# Kaleidoscope.net
KiCad netlist of a schematic drawn in EasyEDA Pro
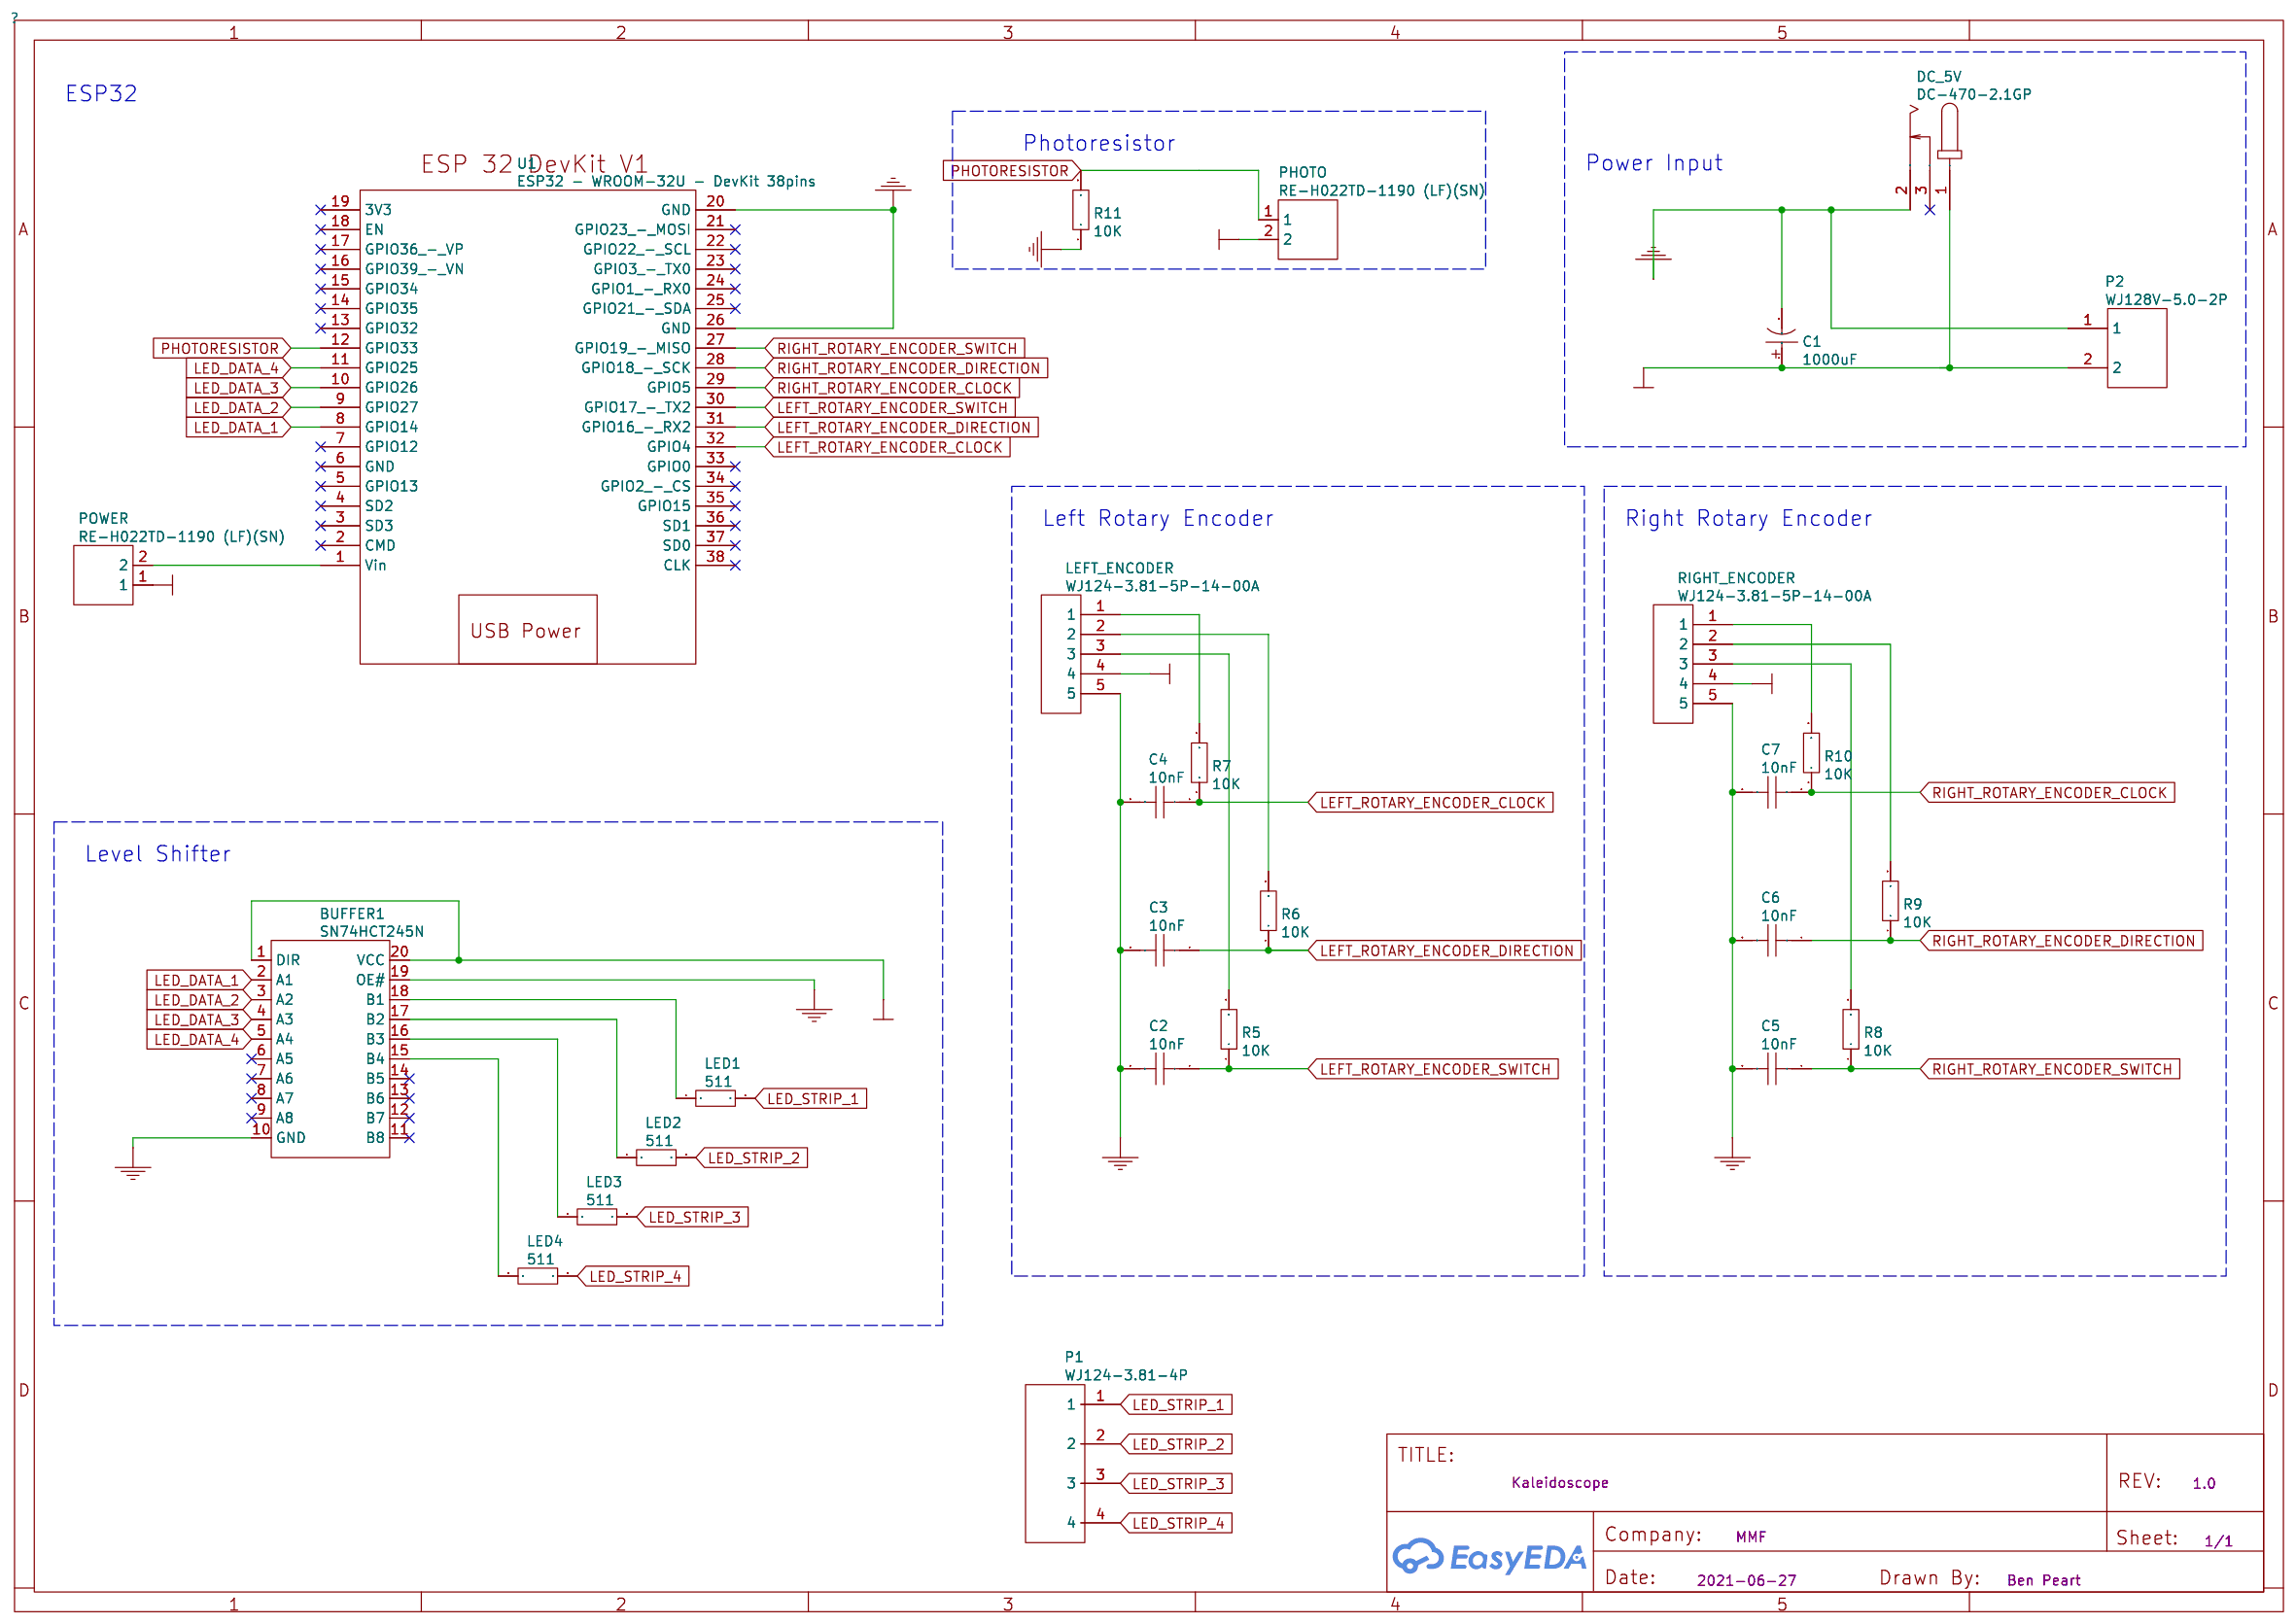
[diagram p0: schematic sheet]

(export (version "E")
  (design (tool "Eeschema 10.0.6"))
  (components
    (comp (ref "BUFFER1")
      (value "SN74HCT245N")
      (footprint "easyedapro:DIP-20_L26.8-W6.4-P2.54-LS7.6-BL")
      (fields (field (name "Manufacturer") "Texas Instruments"))
      (libsource (lib "easyedapro") (part "SN74HCT245N"))
    )
    (comp (ref "C1")
      (value "1000uF")
      (footprint "easyedapro:CAP-TH_BD10.0-P5.00-D1.0-FD")
      (fields (field (name "Manufacturer Part") "25YXJ1000M10X20") (field (name "Manufacturer") "Rubycon"))
      (libsource (lib "easyedapro") (part "1000uF"))
    )
    (comp (ref "C2")
      (value "10nF")
      (footprint "easyedapro:CAP-TH_L5.0-W2.5-P2.54-D0.7")
      (fields
        (field (name "Manufacturer Part") "CC1H103ZA1AD3F4D10MF")
        (field (name "Manufacturer") "Dersonic")
      )
      (libsource (lib "easyedapro") (part "10nF"))
    )
    (comp (ref "C3")
      (value "10nF")
      (footprint "easyedapro:CAP-TH_L5.0-W2.5-P2.54-D0.7")
      (fields
        (field (name "Manufacturer Part") "CC1H103ZA1AD3F4D10MF")
        (field (name "Manufacturer") "Dersonic")
      )
      (libsource (lib "easyedapro") (part "10nF"))
    )
    (comp (ref "C4")
      (value "10nF")
      (footprint "easyedapro:CAP-TH_L5.0-W2.5-P2.54-D0.7")
      (fields
        (field (name "Manufacturer Part") "CC1H103ZA1AD3F4D10MF")
        (field (name "Manufacturer") "Dersonic")
      )
      (libsource (lib "easyedapro") (part "10nF"))
    )
    (comp (ref "C5")
      (value "10nF")
      (footprint "easyedapro:CAP-TH_L5.0-W2.5-P2.54-D0.7")
      (fields
        (field (name "Manufacturer Part") "CC1H103ZA1AD3F4D10MF")
        (field (name "Manufacturer") "Dersonic")
      )
      (libsource (lib "easyedapro") (part "10nF"))
    )
    (comp (ref "C6")
      (value "10nF")
      (footprint "easyedapro:CAP-TH_L5.0-W2.5-P2.54-D0.7")
      (fields
        (field (name "Manufacturer Part") "CC1H103ZA1AD3F4D10MF")
        (field (name "Manufacturer") "Dersonic")
      )
      (libsource (lib "easyedapro") (part "10nF"))
    )
    (comp (ref "C7")
      (value "10nF")
      (footprint "easyedapro:CAP-TH_L5.0-W2.5-P2.54-D0.7")
      (fields
        (field (name "Manufacturer Part") "CC1H103ZA1AD3F4D10MF")
        (field (name "Manufacturer") "Dersonic")
      )
      (libsource (lib "easyedapro") (part "10nF"))
    )
    (comp (ref "DC_5V")
      (value "DC-470-2.1GP")
      (footprint "easyedapro:DC-IN-TH_DC-470-2.1GP")
      (fields (field (name "Manufacturer") "GANGYUAN"))
      (libsource (lib "easyedapro") (part "DC-470-2.1GP"))
    )
    (comp (ref "LED1")
      (value "511")
      (footprint "easyedapro:R0603")
      (fields (field (name "Manufacturer Part") "RC0603FR-07511RL") (field (name "Manufacturer") "YAGEO"))
      (libsource (lib "easyedapro") (part "511"))
    )
    (comp (ref "LED2")
      (value "511")
      (footprint "easyedapro:R0603")
      (fields (field (name "Manufacturer Part") "RC0603FR-07511RL") (field (name "Manufacturer") "YAGEO"))
      (libsource (lib "easyedapro") (part "511"))
    )
    (comp (ref "LED3")
      (value "511")
      (footprint "easyedapro:R0603")
      (fields (field (name "Manufacturer Part") "RC0603FR-07511RL") (field (name "Manufacturer") "YAGEO"))
      (libsource (lib "easyedapro") (part "511"))
    )
    (comp (ref "LED4")
      (value "511")
      (footprint "easyedapro:R0603")
      (fields (field (name "Manufacturer Part") "RC0603FR-07511RL") (field (name "Manufacturer") "YAGEO"))
      (libsource (lib "easyedapro") (part "511"))
    )
    (comp (ref "LEFT_ENCODER")
      (value "WJ124-3.81-5P-14-00A")
      (footprint "easyedapro:CONN-TH_5P-P3.81_KF124-3.81-5P")
      (fields (field (name "Manufacturer") "ReliaPro"))
      (libsource (lib "easyedapro") (part "WJ124-3.81-5P-14-00A"))
    )
    (comp (ref "P1")
      (value "WJ124-3.81-4P")
      (footprint "easyedapro:CONN-TH_4P-P3.81_KF124-3.81-4P")
      (fields (field (name "Manufacturer") "ReliaPro"))
      (libsource (lib "easyedapro") (part "WJ124-3.81-4P"))
    )
    (comp (ref "P2")
      (value "WJ128V-5.0-2P")
      (footprint "easyedapro:CONN-TH_2P-P5.00_WJ128V-5.0-2P")
      (fields (field (name "Manufacturer") "ReliaPro"))
      (libsource (lib "easyedapro") (part "WJ128V-5.0-2P"))
    )
    (comp (ref "PHOTO")
      (value "RE-H022TD-1190 (LF)(SN)")
      (footprint "easyedapro:HDR-TH_2P-P2.54-V")
      (fields (field (name "Manufacturer") "JST Sales America"))
      (libsource (lib "easyedapro") (part "RE-H022TD-1190 (LF)(SN)"))
    )
    (comp (ref "POWER")
      (value "RE-H022TD-1190 (LF)(SN)")
      (footprint "easyedapro:HDR-TH_2P-P2.54-V")
      (fields (field (name "Manufacturer") "JST Sales America"))
      (libsource (lib "easyedapro") (part "RE-H022TD-1190 (LF)(SN)"))
    )
    (comp (ref "R5")
      (value "10K")
      (footprint "easyedapro:R0603")
      (fields (field (name "Manufacturer Part") "ARG03FTC1002") (field (name "Manufacturer") "Viking Tech"))
      (libsource (lib "easyedapro") (part "10K"))
    )
    (comp (ref "R6")
      (value "10K")
      (footprint "easyedapro:R0603")
      (fields (field (name "Manufacturer Part") "ARG03FTC1002") (field (name "Manufacturer") "Viking Tech"))
      (libsource (lib "easyedapro") (part "10K"))
    )
    (comp (ref "R7")
      (value "10K")
      (footprint "easyedapro:R0603")
      (fields (field (name "Manufacturer Part") "ARG03FTC1002") (field (name "Manufacturer") "Viking Tech"))
      (libsource (lib "easyedapro") (part "10K"))
    )
    (comp (ref "R8")
      (value "10K")
      (footprint "easyedapro:R0603")
      (fields (field (name "Manufacturer Part") "ARG03FTC1002") (field (name "Manufacturer") "Viking Tech"))
      (libsource (lib "easyedapro") (part "10K"))
    )
    (comp (ref "R9")
      (value "10K")
      (footprint "easyedapro:R0603")
      (fields (field (name "Manufacturer Part") "ARG03FTC1002") (field (name "Manufacturer") "Viking Tech"))
      (libsource (lib "easyedapro") (part "10K"))
    )
    (comp (ref "R10")
      (value "10K")
      (footprint "easyedapro:R0603")
      (fields (field (name "Manufacturer Part") "ARG03FTC1002") (field (name "Manufacturer") "Viking Tech"))
      (libsource (lib "easyedapro") (part "10K"))
    )
    (comp (ref "R11")
      (value "10K")
      (footprint "easyedapro:R0603")
      (fields (field (name "Manufacturer Part") "ARG03FTC1002") (field (name "Manufacturer") "Viking Tech"))
      (libsource (lib "easyedapro") (part "10K"))
    )
    (comp (ref "RIGHT_ENCODER")
      (value "WJ124-3.81-5P-14-00A")
      (footprint "easyedapro:CONN-TH_5P-P3.81_KF124-3.81-5P")
      (fields (field (name "Manufacturer") "ReliaPro"))
      (libsource (lib "easyedapro") (part "WJ124-3.81-5P-14-00A"))
    )
    (comp (ref "U1")
      (value "ESP32 - WROOM-32U - DevKit 38pins")
      (footprint "easyedapro:ESP32 - WROOM-32U - DEVVKIT 38PIN")
      (libsource (lib "easyedapro") (part "ESP32 - WROOM-32U - DevKit 38pins"))
    )
  )
  (nets
    (net (code "1") (name "+5V") (class "Default")
      (node (ref "BUFFER1") (pin "1") (pinfunction "DIR_1") (pintype "unspecified"))
      (node (ref "BUFFER1") (pin "20") (pinfunction "VCC_20") (pintype "unspecified"))
      (node (ref "C1") (pin "1") (pinfunction "1_1") (pintype "input"))
      (node (ref "DC_5V") (pin "1") (pinfunction "1_1") (pintype "unspecified"))
      (node (ref "LEFT_ENCODER") (pin "4") (pinfunction "4_4") (pintype "unspecified"))
      (node (ref "P2") (pin "2") (pinfunction "2_2") (pintype "unspecified"))
      (node (ref "PHOTO") (pin "2") (pinfunction "2_2") (pintype "unspecified"))
      (node (ref "POWER") (pin "1") (pinfunction "1_1") (pintype "unspecified"))
      (node (ref "RIGHT_ENCODER") (pin "4") (pinfunction "4_4") (pintype "unspecified"))
    )
    (net (code "2") (name "GND") (class "Default")
      (node (ref "BUFFER1") (pin "10") (pinfunction "GND_10") (pintype "unspecified"))
      (node (ref "BUFFER1") (pin "19") (pinfunction "OE#_19") (pintype "unspecified"))
      (node (ref "C1") (pin "2") (pinfunction "2_2") (pintype "input"))
      (node (ref "C2") (pin "2") (pinfunction "2_2") (pintype "unspecified"))
      (node (ref "C3") (pin "2") (pinfunction "2_2") (pintype "unspecified"))
      (node (ref "C4") (pin "2") (pinfunction "2_2") (pintype "unspecified"))
      (node (ref "C5") (pin "2") (pinfunction "2_2") (pintype "unspecified"))
      (node (ref "C6") (pin "2") (pinfunction "2_2") (pintype "unspecified"))
      (node (ref "C7") (pin "2") (pinfunction "2_2") (pintype "unspecified"))
      (node (ref "DC_5V") (pin "2") (pinfunction "2_2") (pintype "unspecified"))
      (node (ref "LEFT_ENCODER") (pin "5") (pinfunction "5_5") (pintype "unspecified"))
      (node (ref "P2") (pin "1") (pinfunction "1_1") (pintype "unspecified"))
      (node (ref "R11") (pin "1") (pinfunction "1_1") (pintype "unspecified"))
      (node (ref "RIGHT_ENCODER") (pin "5") (pinfunction "5_5") (pintype "unspecified"))
      (node (ref "U1") (pin "20") (pinfunction "GND_20") (pintype "unspecified"))
      (node (ref "U1") (pin "26") (pinfunction "GND_26") (pintype "unspecified"))
    )
    (net (code "3") (name "LED_DATA_1") (class "Default")
      (node (ref "BUFFER1") (pin "2") (pinfunction "A1_2") (pintype "unspecified"))
      (node (ref "U1") (pin "8") (pinfunction "GPIO14_8") (pintype "unspecified"))
    )
    (net (code "4") (name "LED_DATA_2") (class "Default")
      (node (ref "BUFFER1") (pin "3") (pinfunction "A2_3") (pintype "unspecified"))
      (node (ref "U1") (pin "9") (pinfunction "GPIO27_9") (pintype "unspecified"))
    )
    (net (code "5") (name "LED_DATA_3") (class "Default")
      (node (ref "BUFFER1") (pin "4") (pinfunction "A3_4") (pintype "unspecified"))
      (node (ref "U1") (pin "10") (pinfunction "GPIO26_10") (pintype "unspecified"))
    )
    (net (code "6") (name "LED_DATA_4") (class "Default")
      (node (ref "BUFFER1") (pin "5") (pinfunction "A4_5") (pintype "unspecified"))
      (node (ref "U1") (pin "11") (pinfunction "GPIO25_11") (pintype "unspecified"))
    )
    (net (code "7") (name "LED_STRIP_1") (class "Default")
      (node (ref "LED1") (pin "2") (pinfunction "2_2") (pintype "input"))
      (node (ref "P1") (pin "1") (pinfunction "1_1") (pintype "input"))
    )
    (net (code "8") (name "LED_STRIP_2") (class "Default")
      (node (ref "LED2") (pin "2") (pinfunction "2_2") (pintype "input"))
      (node (ref "P1") (pin "2") (pinfunction "2_2") (pintype "input"))
    )
    (net (code "9") (name "LED_STRIP_3") (class "Default")
      (node (ref "LED3") (pin "2") (pinfunction "2_2") (pintype "input"))
      (node (ref "P1") (pin "3") (pinfunction "3_3") (pintype "input"))
    )
    (net (code "10") (name "LED_STRIP_4") (class "Default")
      (node (ref "LED4") (pin "2") (pinfunction "2_2") (pintype "input"))
      (node (ref "P1") (pin "4") (pinfunction "4_4") (pintype "input"))
    )
    (net (code "11") (name "LEFT_ROTARY_ENCODER_CLOCK") (class "Default")
      (node (ref "C4") (pin "1") (pinfunction "1_1") (pintype "unspecified"))
      (node (ref "R7") (pin "1") (pinfunction "1_1") (pintype "unspecified"))
      (node (ref "U1") (pin "32") (pinfunction "GPIO4_32") (pintype "unspecified"))
    )
    (net (code "12") (name "LEFT_ROTARY_ENCODER_DIRECTION") (class "Default")
      (node (ref "C3") (pin "1") (pinfunction "1_1") (pintype "unspecified"))
      (node (ref "R6") (pin "1") (pinfunction "1_1") (pintype "unspecified"))
      (node (ref "U1") (pin "31") (pinfunction "GPIO16_-_RX2_31") (pintype "unspecified"))
    )
    (net (code "13") (name "LEFT_ROTARY_ENCODER_SWITCH") (class "Default")
      (node (ref "C2") (pin "1") (pinfunction "1_1") (pintype "unspecified"))
      (node (ref "R5") (pin "1") (pinfunction "1_1") (pintype "unspecified"))
      (node (ref "U1") (pin "30") (pinfunction "GPIO17_-_TX2_30") (pintype "unspecified"))
    )
    (net (code "14") (name "Net-(BUFFER1-B1)") (class "Default")
      (node (ref "BUFFER1") (pin "18") (pinfunction "B1_18") (pintype "unspecified"))
      (node (ref "LED1") (pin "1") (pinfunction "1_1") (pintype "input"))
    )
    (net (code "15") (name "Net-(BUFFER1-B2)") (class "Default")
      (node (ref "BUFFER1") (pin "17") (pinfunction "B2_17") (pintype "unspecified"))
      (node (ref "LED2") (pin "1") (pinfunction "1_1") (pintype "input"))
    )
    (net (code "16") (name "Net-(BUFFER1-B3)") (class "Default")
      (node (ref "BUFFER1") (pin "16") (pinfunction "B3_16") (pintype "unspecified"))
      (node (ref "LED3") (pin "1") (pinfunction "1_1") (pintype "input"))
    )
    (net (code "17") (name "Net-(BUFFER1-B4)") (class "Default")
      (node (ref "BUFFER1") (pin "15") (pinfunction "B4_15") (pintype "unspecified"))
      (node (ref "LED4") (pin "1") (pinfunction "1_1") (pintype "input"))
    )
    (net (code "18") (name "Net-(LEFT_ENCODER-Pad1)") (class "Default")
      (node (ref "LEFT_ENCODER") (pin "1") (pinfunction "1_1") (pintype "unspecified"))
      (node (ref "R7") (pin "2") (pinfunction "2_2") (pintype "unspecified"))
    )
    (net (code "19") (name "Net-(LEFT_ENCODER-Pad2)") (class "Default")
      (node (ref "LEFT_ENCODER") (pin "2") (pinfunction "2_2") (pintype "unspecified"))
      (node (ref "R6") (pin "2") (pinfunction "2_2") (pintype "unspecified"))
    )
    (net (code "20") (name "Net-(LEFT_ENCODER-Pad3)") (class "Default")
      (node (ref "LEFT_ENCODER") (pin "3") (pinfunction "3_3") (pintype "unspecified"))
      (node (ref "R5") (pin "2") (pinfunction "2_2") (pintype "unspecified"))
    )
    (net (code "21") (name "Net-(R8-Pad2)") (class "Default")
      (node (ref "R8") (pin "2") (pinfunction "2_2") (pintype "unspecified"))
      (node (ref "RIGHT_ENCODER") (pin "3") (pinfunction "3_3") (pintype "unspecified"))
    )
    (net (code "22") (name "Net-(R9-Pad2)") (class "Default")
      (node (ref "R9") (pin "2") (pinfunction "2_2") (pintype "unspecified"))
      (node (ref "RIGHT_ENCODER") (pin "2") (pinfunction "2_2") (pintype "unspecified"))
    )
    (net (code "23") (name "Net-(R10-Pad2)") (class "Default")
      (node (ref "R10") (pin "2") (pinfunction "2_2") (pintype "unspecified"))
      (node (ref "RIGHT_ENCODER") (pin "1") (pinfunction "1_1") (pintype "unspecified"))
    )
    (net (code "24") (name "Net-(U1-Vin)") (class "Default")
      (node (ref "POWER") (pin "2") (pinfunction "2_2") (pintype "unspecified"))
      (node (ref "U1") (pin "1") (pinfunction "Vin_1") (pintype "unspecified"))
    )
    (net (code "25") (name "PHOTORESISTOR") (class "Default")
      (node (ref "PHOTO") (pin "1") (pinfunction "1_1") (pintype "unspecified"))
      (node (ref "R11") (pin "2") (pinfunction "2_2") (pintype "unspecified"))
      (node (ref "U1") (pin "12") (pinfunction "GPIO33_12") (pintype "unspecified"))
    )
    (net (code "26") (name "RIGHT_ROTARY_ENCODER_CLOCK") (class "Default")
      (node (ref "C7") (pin "1") (pinfunction "1_1") (pintype "unspecified"))
      (node (ref "R10") (pin "1") (pinfunction "1_1") (pintype "unspecified"))
      (node (ref "U1") (pin "29") (pinfunction "GPIO5_29") (pintype "unspecified"))
    )
    (net (code "27") (name "RIGHT_ROTARY_ENCODER_DIRECTION") (class "Default")
      (node (ref "C6") (pin "1") (pinfunction "1_1") (pintype "unspecified"))
      (node (ref "R9") (pin "1") (pinfunction "1_1") (pintype "unspecified"))
      (node (ref "U1") (pin "28") (pinfunction "GPIO18_-_SCK_28") (pintype "unspecified"))
    )
    (net (code "28") (name "RIGHT_ROTARY_ENCODER_SWITCH") (class "Default")
      (node (ref "C5") (pin "1") (pinfunction "1_1") (pintype "unspecified"))
      (node (ref "R8") (pin "1") (pinfunction "1_1") (pintype "unspecified"))
      (node (ref "U1") (pin "27") (pinfunction "GPIO19_-_MISO_27") (pintype "unspecified"))
    )
    (net (code "29") (name "unconnected-(BUFFER1-A5-Pad6)") (class "Default")
      (node (ref "BUFFER1") (pin "6") (pinfunction "A5_6") (pintype "unspecified+no_connect"))
    )
    (net (code "30") (name "unconnected-(BUFFER1-A6-Pad7)") (class "Default")
      (node (ref "BUFFER1") (pin "7") (pinfunction "A6_7") (pintype "unspecified+no_connect"))
    )
    (net (code "31") (name "unconnected-(BUFFER1-A7-Pad8)") (class "Default")
      (node (ref "BUFFER1") (pin "8") (pinfunction "A7_8") (pintype "unspecified+no_connect"))
    )
    (net (code "32") (name "unconnected-(BUFFER1-A8-Pad9)") (class "Default")
      (node (ref "BUFFER1") (pin "9") (pinfunction "A8_9") (pintype "unspecified+no_connect"))
    )
    (net (code "33") (name "unconnected-(BUFFER1-B5-Pad14)") (class "Default")
      (node (ref "BUFFER1") (pin "14") (pinfunction "B5_14") (pintype "unspecified+no_connect"))
    )
    (net (code "34") (name "unconnected-(BUFFER1-B6-Pad13)") (class "Default")
      (node (ref "BUFFER1") (pin "13") (pinfunction "B6_13") (pintype "unspecified+no_connect"))
    )
    (net (code "35") (name "unconnected-(BUFFER1-B7-Pad12)") (class "Default")
      (node (ref "BUFFER1") (pin "12") (pinfunction "B7_12") (pintype "unspecified+no_connect"))
    )
    (net (code "36") (name "unconnected-(BUFFER1-B8-Pad11)") (class "Default")
      (node (ref "BUFFER1") (pin "11") (pinfunction "B8_11") (pintype "unspecified+no_connect"))
    )
    (net (code "37") (name "unconnected-(DC_5V-Pad3)") (class "Default")
      (node (ref "DC_5V") (pin "3") (pinfunction "3_3") (pintype "unspecified+no_connect"))
    )
    (net (code "38") (name "unconnected-(U1-3V3-Pad19)") (class "Default")
      (node (ref "U1") (pin "19") (pinfunction "3V3_19") (pintype "unspecified+no_connect"))
    )
    (net (code "39") (name "unconnected-(U1-CLK-Pad38)") (class "Default")
      (node (ref "U1") (pin "38") (pinfunction "CLK_38") (pintype "unspecified+no_connect"))
    )
    (net (code "40") (name "unconnected-(U1-CMD-Pad2)") (class "Default")
      (node (ref "U1") (pin "2") (pinfunction "CMD_2") (pintype "unspecified+no_connect"))
    )
    (net (code "41") (name "unconnected-(U1-EN-Pad18)") (class "Default")
      (node (ref "U1") (pin "18") (pinfunction "EN_18") (pintype "unspecified+no_connect"))
    )
    (net (code "42") (name "unconnected-(U1-GND-Pad6)") (class "Default")
      (node (ref "U1") (pin "6") (pinfunction "GND_6") (pintype "unspecified+no_connect"))
    )
    (net (code "43") (name "unconnected-(U1-GPIO0-Pad33)") (class "Default")
      (node (ref "U1") (pin "33") (pinfunction "GPIO0_33") (pintype "unspecified+no_connect"))
    )
    (net (code "44") (name "unconnected-(U1-GPIO1_-_RX0-Pad24)") (class "Default")
      (node (ref "U1") (pin "24") (pinfunction "GPIO1_-_RX0_24") (pintype "unspecified+no_connect"))
    )
    (net (code "45") (name "unconnected-(U1-GPIO2_-_CS-Pad34)") (class "Default")
      (node (ref "U1") (pin "34") (pinfunction "GPIO2_-_CS_34") (pintype "unspecified+no_connect"))
    )
    (net (code "46") (name "unconnected-(U1-GPIO3_-_TX0-Pad23)") (class "Default")
      (node (ref "U1") (pin "23") (pinfunction "GPIO3_-_TX0_23") (pintype "unspecified+no_connect"))
    )
    (net (code "47") (name "unconnected-(U1-GPIO12-Pad7)") (class "Default")
      (node (ref "U1") (pin "7") (pinfunction "GPIO12_7") (pintype "unspecified+no_connect"))
    )
    (net (code "48") (name "unconnected-(U1-GPIO13-Pad5)") (class "Default")
      (node (ref "U1") (pin "5") (pinfunction "GPIO13_5") (pintype "unspecified+no_connect"))
    )
    (net (code "49") (name "unconnected-(U1-GPIO15-Pad35)") (class "Default")
      (node (ref "U1") (pin "35") (pinfunction "GPIO15_35") (pintype "unspecified+no_connect"))
    )
    (net (code "50") (name "unconnected-(U1-GPIO21_-_SDA-Pad25)") (class "Default")
      (node (ref "U1") (pin "25") (pinfunction "GPIO21_-_SDA_25") (pintype "unspecified+no_connect"))
    )
    (net (code "51") (name "unconnected-(U1-GPIO22_-_SCL-Pad22)") (class "Default")
      (node (ref "U1") (pin "22") (pinfunction "GPIO22_-_SCL_22") (pintype "unspecified+no_connect"))
    )
    (net (code "52") (name "unconnected-(U1-GPIO23_-_MOSI-Pad21)") (class "Default")
      (node (ref "U1") (pin "21") (pinfunction "GPIO23_-_MOSI_21") (pintype "unspecified+no_connect"))
    )
    (net (code "53") (name "unconnected-(U1-GPIO32-Pad13)") (class "Default")
      (node (ref "U1") (pin "13") (pinfunction "GPIO32_13") (pintype "unspecified+no_connect"))
    )
    (net (code "54") (name "unconnected-(U1-GPIO34-Pad15)") (class "Default")
      (node (ref "U1") (pin "15") (pinfunction "GPIO34_15") (pintype "unspecified+no_connect"))
    )
    (net (code "55") (name "unconnected-(U1-GPIO35-Pad14)") (class "Default")
      (node (ref "U1") (pin "14") (pinfunction "GPIO35_14") (pintype "unspecified+no_connect"))
    )
    (net (code "56") (name "unconnected-(U1-GPIO36_-_VP-Pad17)") (class "Default")
      (node (ref "U1") (pin "17") (pinfunction "GPIO36_-_VP_17") (pintype "unspecified+no_connect"))
    )
    (net (code "57") (name "unconnected-(U1-GPIO39_-_VN-Pad16)") (class "Default")
      (node (ref "U1") (pin "16") (pinfunction "GPIO39_-_VN_16") (pintype "unspecified+no_connect"))
    )
    (net (code "58") (name "unconnected-(U1-SD0-Pad37)") (class "Default")
      (node (ref "U1") (pin "37") (pinfunction "SD0_37") (pintype "unspecified+no_connect"))
    )
    (net (code "59") (name "unconnected-(U1-SD1-Pad36)") (class "Default")
      (node (ref "U1") (pin "36") (pinfunction "SD1_36") (pintype "unspecified+no_connect"))
    )
    (net (code "60") (name "unconnected-(U1-SD2-Pad4)") (class "Default")
      (node (ref "U1") (pin "4") (pinfunction "SD2_4") (pintype "unspecified+no_connect"))
    )
    (net (code "61") (name "unconnected-(U1-SD3-Pad3)") (class "Default")
      (node (ref "U1") (pin "3") (pinfunction "SD3_3") (pintype "unspecified+no_connect"))
    )
  )
)
